# tick-display-mk-5.net
KiCad netlist of a schematic drawn in EAGLE
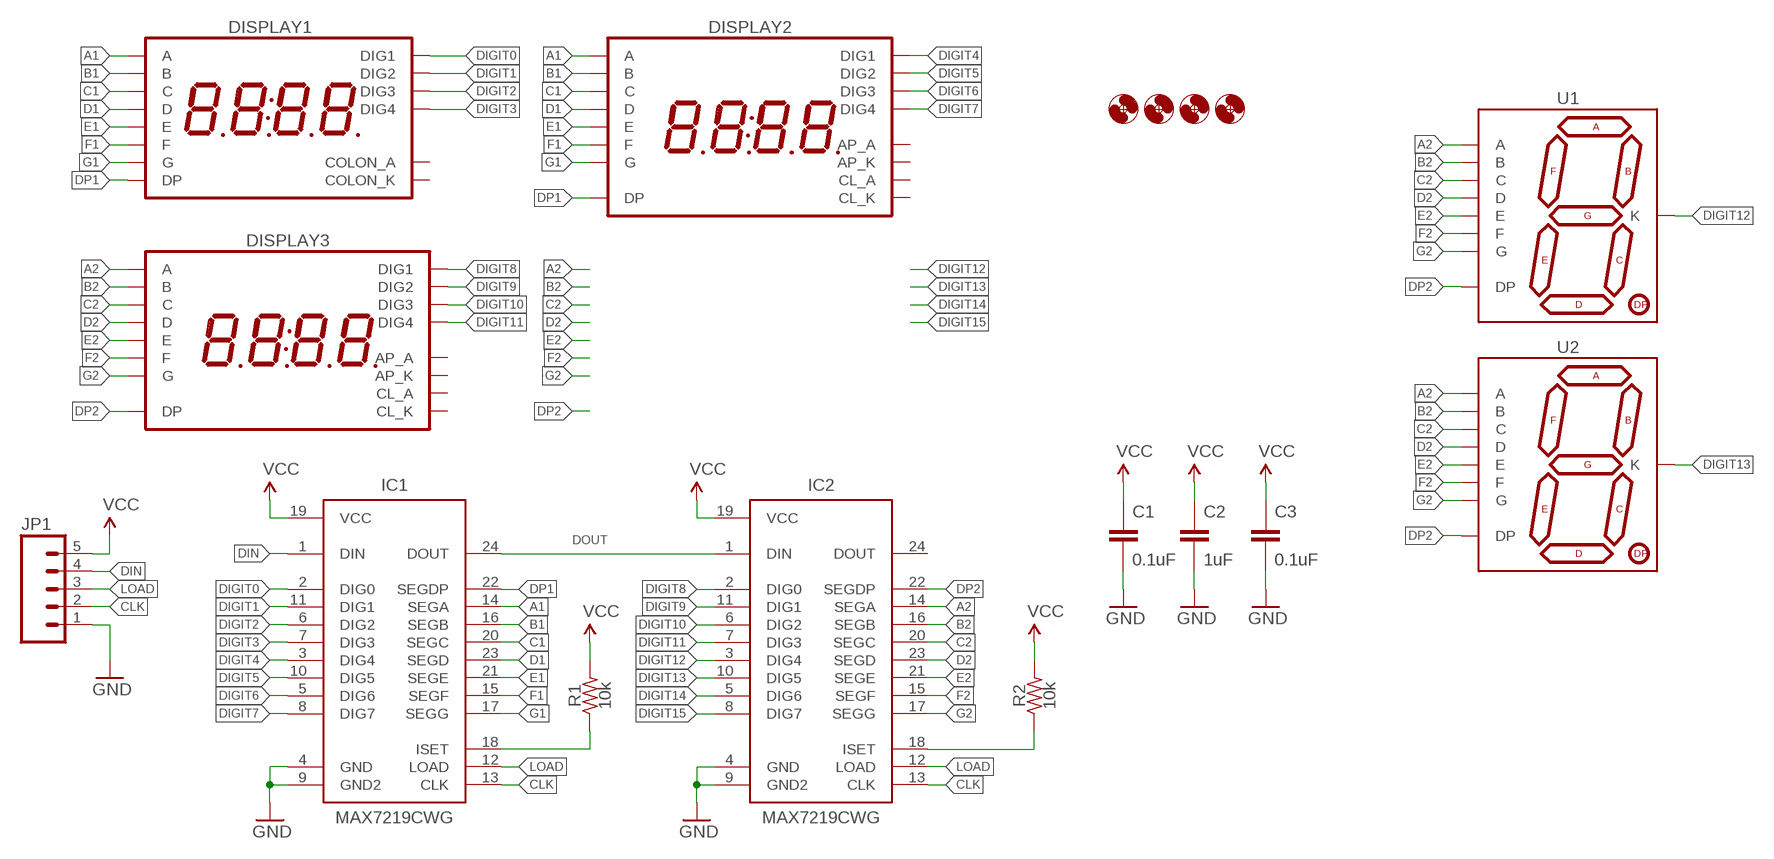
[diagram p0: schematic, sheet 1]

(export (version "E")
  (design (tool "Eeschema 10.0.6"))
  (components
    (comp (ref "C1")
      (value "0.1uF")
      (footprint "eagle-import:C025-024X044")
      (libsource (lib "eagle-import") (part "CAPACITOR-CERAMIC025-024X044"))
    )
    (comp (ref "C2")
      (value "1uF")
      (footprint "eagle-import:C025-024X044")
      (libsource (lib "eagle-import") (part "CAPACITOR-CERAMIC025-024X044"))
    )
    (comp (ref "C3")
      (value "0.1uF")
      (footprint "eagle-import:C025-024X044")
      (libsource (lib "eagle-import") (part "CAPACITOR-CERAMIC025-024X044"))
    )
    (comp (ref "DISPLAY1")
      (value "7SEG_4DIGIT_COLON14.2MM-CC")
      (footprint "eagle-import:7SEG_4DIG_0.56IN_14MM_ADAFRUIT")
      (libsource (lib "eagle-import") (part "7SEG_4DIGIT_COLON14.2MM-CC"))
    )
    (comp (ref "DISPLAY2")
      (value "7SEG_4DIGIT_COLON_APOS")
      (footprint "eagle-import:7SEG_4DIG_10MM")
      (libsource (lib "eagle-import") (part "7SEG_4DIGIT_COLON_APOS"))
    )
    (comp (ref "DISPLAY3")
      (value "7SEG_4DIGIT_COLON_APOS")
      (footprint "eagle-import:7SEG_4DIG_10MM")
      (libsource (lib "eagle-import") (part "7SEG_4DIGIT_COLON_APOS"))
    )
    (comp (ref "H1")
      (value "HOLE#2")
      (footprint "eagle-import:HOLE-#2")
      (libsource (lib "eagle-import") (part "HOLE#2"))
    )
    (comp (ref "H2")
      (value "HOLE#2")
      (footprint "eagle-import:HOLE-#2")
      (libsource (lib "eagle-import") (part "HOLE#2"))
    )
    (comp (ref "H3")
      (value "HOLE#2")
      (footprint "eagle-import:HOLE-#2")
      (libsource (lib "eagle-import") (part "HOLE#2"))
    )
    (comp (ref "H4")
      (value "HOLE#2")
      (footprint "eagle-import:HOLE-#2")
      (libsource (lib "eagle-import") (part "HOLE#2"))
    )
    (comp (ref "IC1")
      (value "MAX7219CWG")
      (footprint "eagle-import:SO24W")
      (libsource (lib "eagle-import") (part "MAX7219SOIC-W"))
    )
    (comp (ref "IC2")
      (value "MAX7219CWG")
      (footprint "eagle-import:SO24W")
      (libsource (lib "eagle-import") (part "MAX7219SOIC-W"))
    )
    (comp (ref "JP1")
      (value "M05JST-PH-VERT-PTH")
      (footprint "eagle-import:JST-5-PH-VERT-PTH")
      (libsource (lib "eagle-import") (part "M05JST-PH-VERT-PTH"))
    )
    (comp (ref "R1")
      (value "10k")
      (footprint "eagle-import:RESISTOR-AXIAL-PTH-5.08MM")
      (libsource (lib "eagle-import") (part "RESISTORPTH-AXIAL-5.08MM"))
    )
    (comp (ref "R2")
      (value "10k")
      (footprint "eagle-import:RESISTOR-AXIAL-PTH-5.08MM")
      (libsource (lib "eagle-import") (part "RESISTORPTH-AXIAL-5.08MM"))
    )
    (comp (ref "U1")
      (value "7SEG_1DIGPTH-10MM")
      (footprint "eagle-import:7SEG_1DIG_10MM")
      (libsource (lib "eagle-import") (part "7SEG_1DIGPTH-10MM"))
    )
    (comp (ref "U2")
      (value "7SEG_1DIGPTH-10MM")
      (footprint "eagle-import:7SEG_1DIG_10MM")
      (libsource (lib "eagle-import") (part "7SEG_1DIGPTH-10MM"))
    )
  )
  (nets
    (net (code "1") (name "/DOUT") (class "Default")
      (node (ref "IC1") (pin "24") (pinfunction "DOUT_24") (pintype "bidirectional"))
      (node (ref "IC2") (pin "1") (pinfunction "DIN_1") (pintype "bidirectional"))
    )
    (net (code "2") (name "A1") (class "Default")
      (node (ref "DISPLAY1") (pin "P$13") (pinfunction "A_P$13") (pintype "passive"))
      (node (ref "DISPLAY2") (pin "14") (pinfunction "A_14") (pintype "passive"))
      (node (ref "IC1") (pin "14") (pinfunction "SEGA_14") (pintype "bidirectional"))
    )
    (net (code "3") (name "A2") (class "Default")
      (node (ref "DISPLAY3") (pin "14") (pinfunction "A_14") (pintype "passive"))
      (node (ref "IC2") (pin "14") (pinfunction "SEGA_14") (pintype "bidirectional"))
      (node (ref "U1") (pin "10") (pinfunction "A_10") (pintype "bidirectional"))
      (node (ref "U2") (pin "10") (pinfunction "A_10") (pintype "bidirectional"))
    )
    (net (code "4") (name "B1") (class "Default")
      (node (ref "DISPLAY1") (pin "P$9") (pinfunction "B_P$9") (pintype "passive"))
      (node (ref "DISPLAY2") (pin "16") (pinfunction "B_16") (pintype "passive"))
      (node (ref "IC1") (pin "16") (pinfunction "SEGB_16") (pintype "bidirectional"))
    )
    (net (code "5") (name "B2") (class "Default")
      (node (ref "DISPLAY3") (pin "16") (pinfunction "B_16") (pintype "passive"))
      (node (ref "IC2") (pin "16") (pinfunction "SEGB_16") (pintype "bidirectional"))
      (node (ref "U1") (pin "9") (pinfunction "B_9") (pintype "bidirectional"))
      (node (ref "U2") (pin "9") (pinfunction "B_9") (pintype "bidirectional"))
    )
    (net (code "6") (name "C1") (class "Default")
      (node (ref "DISPLAY1") (pin "P$4") (pinfunction "C_P$4") (pintype "passive"))
      (node (ref "DISPLAY2") (pin "13") (pinfunction "C_13") (pintype "passive"))
      (node (ref "IC1") (pin "20") (pinfunction "SEGC_20") (pintype "bidirectional"))
    )
    (net (code "7") (name "C2") (class "Default")
      (node (ref "DISPLAY3") (pin "13") (pinfunction "C_13") (pintype "passive"))
      (node (ref "IC2") (pin "20") (pinfunction "SEGC_20") (pintype "bidirectional"))
      (node (ref "U1") (pin "8") (pinfunction "C_8") (pintype "bidirectional"))
      (node (ref "U2") (pin "8") (pinfunction "C_8") (pintype "bidirectional"))
    )
    (net (code "8") (name "CLK") (class "Default")
      (node (ref "IC1") (pin "13") (pinfunction "CLK_13") (pintype "bidirectional"))
      (node (ref "IC2") (pin "13") (pinfunction "CLK_13") (pintype "bidirectional"))
      (node (ref "JP1") (pin "2") (pinfunction "2_2") (pintype "passive"))
    )
    (net (code "9") (name "D1") (class "Default")
      (node (ref "DISPLAY1") (pin "P$2") (pinfunction "D_P$2") (pintype "passive"))
      (node (ref "DISPLAY2") (pin "3") (pinfunction "D_3") (pintype "passive"))
      (node (ref "IC1") (pin "23") (pinfunction "SEGD_23") (pintype "bidirectional"))
    )
    (net (code "10") (name "D2") (class "Default")
      (node (ref "DISPLAY3") (pin "3") (pinfunction "D_3") (pintype "passive"))
      (node (ref "IC2") (pin "23") (pinfunction "SEGD_23") (pintype "bidirectional"))
      (node (ref "U1") (pin "5") (pinfunction "D_5") (pintype "bidirectional"))
      (node (ref "U2") (pin "5") (pinfunction "D_5") (pintype "bidirectional"))
    )
    (net (code "11") (name "DIGIT0") (class "Default")
      (node (ref "DISPLAY1") (pin "P$14") (pinfunction "DIG1_P$14") (pintype "passive"))
      (node (ref "IC1") (pin "2") (pinfunction "DIG0_2") (pintype "bidirectional"))
    )
    (net (code "12") (name "DIGIT1") (class "Default")
      (node (ref "DISPLAY1") (pin "P$11") (pinfunction "DIG2_P$11") (pintype "passive"))
      (node (ref "IC1") (pin "11") (pinfunction "DIG1_11") (pintype "bidirectional"))
    )
    (net (code "13") (name "DIGIT2") (class "Default")
      (node (ref "DISPLAY1") (pin "P$10") (pinfunction "DIG3_P$10") (pintype "passive"))
      (node (ref "IC1") (pin "6") (pinfunction "DIG2_6") (pintype "bidirectional"))
    )
    (net (code "14") (name "DIGIT3") (class "Default")
      (node (ref "DISPLAY1") (pin "P$6") (pinfunction "DIG4_P$6") (pintype "passive"))
      (node (ref "IC1") (pin "7") (pinfunction "DIG3_7") (pintype "bidirectional"))
    )
    (net (code "15") (name "DIGIT4") (class "Default")
      (node (ref "DISPLAY2") (pin "1") (pinfunction "DIG1_1") (pintype "passive"))
      (node (ref "IC1") (pin "3") (pinfunction "DIG4_3") (pintype "bidirectional"))
    )
    (net (code "16") (name "DIGIT5") (class "Default")
      (node (ref "DISPLAY2") (pin "2") (pinfunction "DIG2_2") (pintype "passive"))
      (node (ref "IC1") (pin "10") (pinfunction "DIG5_10") (pintype "bidirectional"))
    )
    (net (code "17") (name "DIGIT6") (class "Default")
      (node (ref "DISPLAY2") (pin "6") (pinfunction "DIG3_6") (pintype "passive"))
      (node (ref "IC1") (pin "5") (pinfunction "DIG6_5") (pintype "bidirectional"))
    )
    (net (code "18") (name "DIGIT7") (class "Default")
      (node (ref "DISPLAY2") (pin "8") (pinfunction "DIG4_8") (pintype "passive"))
      (node (ref "IC1") (pin "8") (pinfunction "DIG7_8") (pintype "bidirectional"))
    )
    (net (code "19") (name "DIGIT8") (class "Default")
      (node (ref "DISPLAY3") (pin "1") (pinfunction "DIG1_1") (pintype "passive"))
      (node (ref "IC2") (pin "2") (pinfunction "DIG0_2") (pintype "bidirectional"))
    )
    (net (code "20") (name "DIGIT9") (class "Default")
      (node (ref "DISPLAY3") (pin "2") (pinfunction "DIG2_2") (pintype "passive"))
      (node (ref "IC2") (pin "11") (pinfunction "DIG1_11") (pintype "bidirectional"))
    )
    (net (code "21") (name "DIGIT10") (class "Default")
      (node (ref "DISPLAY3") (pin "6") (pinfunction "DIG3_6") (pintype "passive"))
      (node (ref "IC2") (pin "6") (pinfunction "DIG2_6") (pintype "bidirectional"))
    )
    (net (code "22") (name "DIGIT11") (class "Default")
      (node (ref "DISPLAY3") (pin "8") (pinfunction "DIG4_8") (pintype "passive"))
      (node (ref "IC2") (pin "7") (pinfunction "DIG3_7") (pintype "bidirectional"))
    )
    (net (code "23") (name "DIGIT12") (class "Default")
      (node (ref "IC2") (pin "3") (pinfunction "DIG4_3") (pintype "bidirectional"))
      (node (ref "U1") (pin "1") (pinfunction "K_1") (pintype "bidirectional"))
      (node (ref "U1") (pin "6") (pinfunction "K_6") (pintype "bidirectional"))
    )
    (net (code "24") (name "DIGIT13") (class "Default")
      (node (ref "IC2") (pin "10") (pinfunction "DIG5_10") (pintype "bidirectional"))
      (node (ref "U2") (pin "1") (pinfunction "K_1") (pintype "bidirectional"))
      (node (ref "U2") (pin "6") (pinfunction "K_6") (pintype "bidirectional"))
    )
    (net (code "25") (name "DIGIT14") (class "Default")
      (node (ref "IC2") (pin "5") (pinfunction "DIG6_5") (pintype "bidirectional"))
    )
    (net (code "26") (name "DIGIT15") (class "Default")
      (node (ref "IC2") (pin "8") (pinfunction "DIG7_8") (pintype "bidirectional"))
    )
    (net (code "27") (name "DIN") (class "Default")
      (node (ref "IC1") (pin "1") (pinfunction "DIN_1") (pintype "bidirectional"))
      (node (ref "JP1") (pin "4") (pinfunction "4_4") (pintype "passive"))
    )
    (net (code "28") (name "DP1") (class "Default")
      (node (ref "DISPLAY1") (pin "P$3") (pinfunction "DP_P$3") (pintype "passive"))
      (node (ref "DISPLAY2") (pin "7") (pinfunction "DP_7") (pintype "passive"))
      (node (ref "IC1") (pin "22") (pinfunction "SEGDP_22") (pintype "bidirectional"))
    )
    (net (code "29") (name "DP2") (class "Default")
      (node (ref "DISPLAY3") (pin "7") (pinfunction "DP_7") (pintype "passive"))
      (node (ref "IC2") (pin "22") (pinfunction "SEGDP_22") (pintype "bidirectional"))
      (node (ref "U1") (pin "7") (pinfunction "DP_7") (pintype "bidirectional"))
      (node (ref "U2") (pin "7") (pinfunction "DP_7") (pintype "bidirectional"))
    )
    (net (code "30") (name "E1") (class "Default")
      (node (ref "DISPLAY1") (pin "P$1") (pinfunction "E_P$1") (pintype "passive"))
      (node (ref "DISPLAY2") (pin "5") (pinfunction "E_5") (pintype "passive"))
      (node (ref "IC1") (pin "21") (pinfunction "SEGE_21") (pintype "bidirectional"))
    )
    (net (code "31") (name "E2") (class "Default")
      (node (ref "DISPLAY3") (pin "5") (pinfunction "E_5") (pintype "passive"))
      (node (ref "IC2") (pin "21") (pinfunction "SEGE_21") (pintype "bidirectional"))
      (node (ref "U1") (pin "4") (pinfunction "E_4") (pintype "bidirectional"))
      (node (ref "U2") (pin "4") (pinfunction "E_4") (pintype "bidirectional"))
    )
    (net (code "32") (name "F1") (class "Default")
      (node (ref "DISPLAY1") (pin "P$12") (pinfunction "F_P$12") (pintype "passive"))
      (node (ref "DISPLAY2") (pin "11") (pinfunction "F_11") (pintype "passive"))
      (node (ref "IC1") (pin "15") (pinfunction "SEGF_15") (pintype "bidirectional"))
    )
    (net (code "33") (name "F2") (class "Default")
      (node (ref "DISPLAY3") (pin "11") (pinfunction "F_11") (pintype "passive"))
      (node (ref "IC2") (pin "15") (pinfunction "SEGF_15") (pintype "bidirectional"))
      (node (ref "U1") (pin "2") (pinfunction "F_2") (pintype "bidirectional"))
      (node (ref "U2") (pin "2") (pinfunction "F_2") (pintype "bidirectional"))
    )
    (net (code "34") (name "G1") (class "Default")
      (node (ref "DISPLAY1") (pin "P$5") (pinfunction "G_P$5") (pintype "passive"))
      (node (ref "DISPLAY2") (pin "15") (pinfunction "G_15") (pintype "passive"))
      (node (ref "IC1") (pin "17") (pinfunction "SEGG_17") (pintype "bidirectional"))
    )
    (net (code "35") (name "G2") (class "Default")
      (node (ref "DISPLAY3") (pin "15") (pinfunction "G_15") (pintype "passive"))
      (node (ref "IC2") (pin "17") (pinfunction "SEGG_17") (pintype "bidirectional"))
      (node (ref "U1") (pin "3") (pinfunction "G_3") (pintype "bidirectional"))
      (node (ref "U2") (pin "3") (pinfunction "G_3") (pintype "bidirectional"))
    )
    (net (code "36") (name "GND") (class "Default")
      (node (ref "C1") (pin "2") (pinfunction "2_2") (pintype "passive"))
      (node (ref "C2") (pin "2") (pinfunction "2_2") (pintype "passive"))
      (node (ref "C3") (pin "2") (pinfunction "2_2") (pintype "passive"))
      (node (ref "IC1") (pin "4") (pinfunction "GND_4") (pintype "bidirectional"))
      (node (ref "IC1") (pin "9") (pinfunction "GND2_9") (pintype "bidirectional"))
      (node (ref "IC2") (pin "4") (pinfunction "GND_4") (pintype "bidirectional"))
      (node (ref "IC2") (pin "9") (pinfunction "GND2_9") (pintype "bidirectional"))
      (node (ref "JP1") (pin "1") (pinfunction "1_1") (pintype "passive"))
    )
    (net (code "37") (name "LOAD") (class "Default")
      (node (ref "IC1") (pin "12") (pinfunction "LOAD_12") (pintype "bidirectional"))
      (node (ref "IC2") (pin "12") (pinfunction "LOAD_12") (pintype "bidirectional"))
      (node (ref "JP1") (pin "3") (pinfunction "3_3") (pintype "passive"))
    )
    (net (code "38") (name "Net-(IC1-ISET)") (class "Default")
      (node (ref "IC1") (pin "18") (pinfunction "ISET_18") (pintype "bidirectional"))
      (node (ref "R1") (pin "P$1") (pinfunction "1_P$1") (pintype "passive"))
    )
    (net (code "39") (name "Net-(IC2-ISET)") (class "Default")
      (node (ref "IC2") (pin "18") (pinfunction "ISET_18") (pintype "bidirectional"))
      (node (ref "R2") (pin "P$1") (pinfunction "1_P$1") (pintype "passive"))
    )
    (net (code "40") (name "VCC") (class "Default")
      (node (ref "C1") (pin "1") (pinfunction "1_1") (pintype "passive"))
      (node (ref "C2") (pin "1") (pinfunction "1_1") (pintype "passive"))
      (node (ref "C3") (pin "1") (pinfunction "1_1") (pintype "passive"))
      (node (ref "IC1") (pin "19") (pinfunction "VCC_19") (pintype "bidirectional"))
      (node (ref "IC2") (pin "19") (pinfunction "VCC_19") (pintype "bidirectional"))
      (node (ref "JP1") (pin "5") (pinfunction "5_5") (pintype "passive"))
      (node (ref "R1") (pin "P$2") (pinfunction "2_P$2") (pintype "passive"))
      (node (ref "R2") (pin "P$2") (pinfunction "2_P$2") (pintype "passive"))
    )
    (net (code "41") (name "unconnected-(DISPLAY1-COLON_A-PadP$8)") (class "Default")
      (node (ref "DISPLAY1") (pin "P$8") (pinfunction "COLON_A_P$8") (pintype "passive"))
    )
    (net (code "42") (name "unconnected-(DISPLAY1-COLON_K-PadP$7)") (class "Default")
      (node (ref "DISPLAY1") (pin "P$7") (pinfunction "COLON_K_P$7") (pintype "passive"))
    )
    (net (code "43") (name "unconnected-(DISPLAY2-AP_A-Pad10)") (class "Default")
      (node (ref "DISPLAY2") (pin "10") (pinfunction "AP_A_10") (pintype "bidirectional"))
    )
    (net (code "44") (name "unconnected-(DISPLAY2-AP_K-Pad9)") (class "Default")
      (node (ref "DISPLAY2") (pin "9") (pinfunction "AP_K_9") (pintype "bidirectional"))
    )
    (net (code "45") (name "unconnected-(DISPLAY2-CL_A-Pad4)") (class "Default")
      (node (ref "DISPLAY2") (pin "4") (pinfunction "CL_A_4") (pintype "passive"))
    )
    (net (code "46") (name "unconnected-(DISPLAY2-CL_K-Pad12)") (class "Default")
      (node (ref "DISPLAY2") (pin "12") (pinfunction "CL_K_12") (pintype "passive"))
    )
    (net (code "47") (name "unconnected-(DISPLAY3-AP_A-Pad10)") (class "Default")
      (node (ref "DISPLAY3") (pin "10") (pinfunction "AP_A_10") (pintype "bidirectional"))
    )
    (net (code "48") (name "unconnected-(DISPLAY3-AP_K-Pad9)") (class "Default")
      (node (ref "DISPLAY3") (pin "9") (pinfunction "AP_K_9") (pintype "bidirectional"))
    )
    (net (code "49") (name "unconnected-(DISPLAY3-CL_A-Pad4)") (class "Default")
      (node (ref "DISPLAY3") (pin "4") (pinfunction "CL_A_4") (pintype "passive"))
    )
    (net (code "50") (name "unconnected-(DISPLAY3-CL_K-Pad12)") (class "Default")
      (node (ref "DISPLAY3") (pin "12") (pinfunction "CL_K_12") (pintype "passive"))
    )
    (net (code "51") (name "unconnected-(IC2-DOUT-Pad24)") (class "Default")
      (node (ref "IC2") (pin "24") (pinfunction "DOUT_24") (pintype "bidirectional"))
    )
  )
)
